# DualLink.net
KiCad netlist of a schematic drawn in Altium Designer
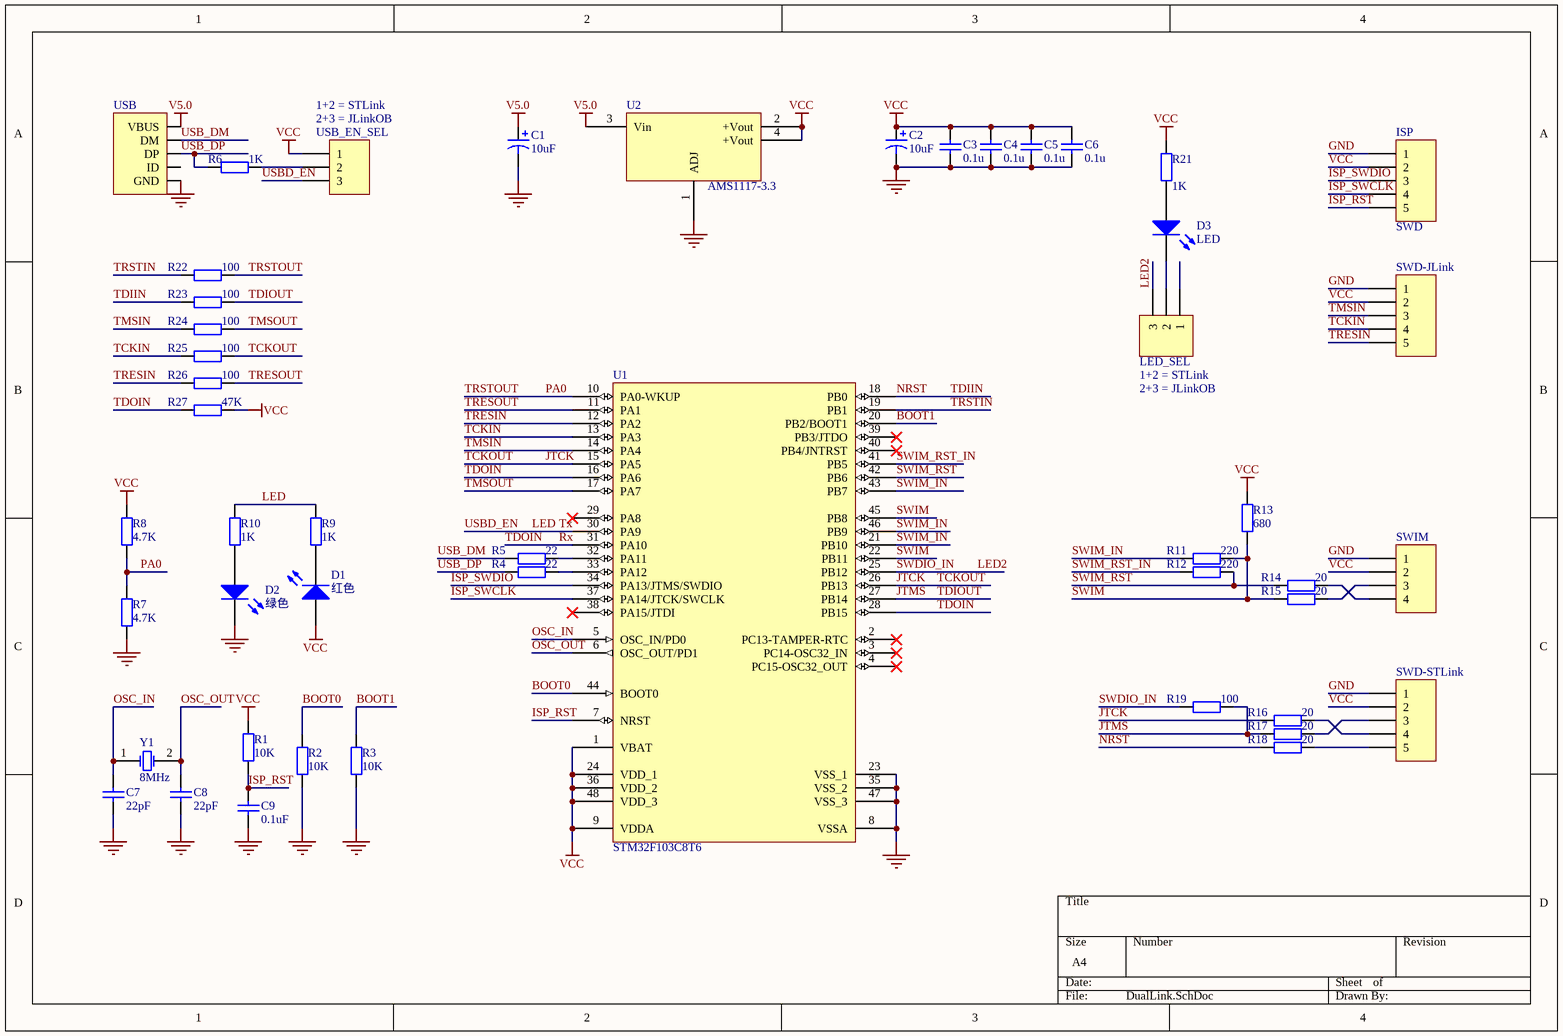
[diagram p0: DualLink.SchDoc]

(export (version "E")
  (design (tool "Eeschema 10.0.6"))
  (components
    (comp (ref "C1")
      (value "10uF")
      (footprint "C1206A")
      (description "Polarized Capacitor (Surface Mount)")
      (fields (field (name "PUBLISHER") "Altium Limited"))
      (libsource (lib "altium-import") (part "root_3_Cap Pol3_"))
    )
    (comp (ref "C2")
      (value "10uF")
      (footprint "C1206A")
      (description "Polarized Capacitor (Surface Mount)")
      (fields (field (name "PUBLISHER") "Altium Limited"))
      (libsource (lib "altium-import") (part "root_3_Cap Pol3_"))
    )
    (comp (ref "C3")
      (value "0.1u")
      (description "Capacitor")
      (fields (field (name "PUBLISHER") "Altium Limited"))
      (libsource (lib "altium-import") (part "root_3_Cap_"))
    )
    (comp (ref "C4")
      (value "0.1u")
      (description "Capacitor")
      (fields (field (name "PUBLISHER") "Altium Limited"))
      (libsource (lib "altium-import") (part "root_3_Cap_"))
    )
    (comp (ref "C5")
      (value "0.1u")
      (description "Capacitor")
      (fields (field (name "PUBLISHER") "Altium Limited"))
      (libsource (lib "altium-import") (part "root_3_Cap_"))
    )
    (comp (ref "C6")
      (value "0.1u")
      (description "Capacitor")
      (fields (field (name "PUBLISHER") "Altium Limited"))
      (libsource (lib "altium-import") (part "root_3_Cap_"))
    )
    (comp (ref "C7")
      (value "22pF")
      (footprint "C0603")
      (description "Capacitor")
      (fields (field (name "PUBLISHER") "Altium Limited"))
      (libsource (lib "altium-import") (part "root_3_Cap_"))
    )
    (comp (ref "C8")
      (value "22pF")
      (footprint "C0603")
      (description "Capacitor")
      (fields (field (name "PUBLISHER") "Altium Limited"))
      (libsource (lib "altium-import") (part "root_3_Cap_"))
    )
    (comp (ref "C9")
      (value "0.1uF")
      (footprint "C0603")
      (description "Capacitor")
      (fields (field (name "PUBLISHER") "Altium Limited"))
      (libsource (lib "altium-import") (part "root_3_Cap_"))
    )
    (comp (ref "D1")
      (value "红色")
      (footprint "LED0603")
      (description "Typical RED, GREEN, YELLOW, AMBER GaAs LED")
      (fields (field (name "PUBLISHER") "Altium Limited"))
      (libsource (lib "altium-import") (part "root_1_LED2_"))
    )
    (comp (ref "D2")
      (value "绿色")
      (footprint "LED0603")
      (description "Typical RED, GREEN, YELLOW, AMBER GaAs LED")
      (fields (field (name "PUBLISHER") "Altium Limited"))
      (libsource (lib "altium-import") (part "root_3_LED2_"))
    )
    (comp (ref "D3")
      (value "LED")
      (footprint "LED0603")
      (description "Typical RED, GREEN, YELLOW, AMBER GaAs LED")
      (fields (field (name "PUBLISHER") "Altium Limited"))
      (libsource (lib "altium-import") (part "root_3_LED2_"))
    )
    (comp (ref "ISP")
      (value "SWD")
      (footprint "HDR1X5")
      (description "Header, 5-Pin")
      (fields (field (name "PUBLISHER") "Altium Limited"))
      (libsource (lib "altium-import") (part "root_0_Header 5_"))
    )
    (comp (ref "LED_SEL")
      (value "~")
      (footprint "HDR1X3")
      (description "Header, 3-Pin")
      (fields (field (name "PUBLISHER") "Altium Limited"))
      (libsource (lib "altium-import") (part "root_3_Header 3_"))
    )
    (comp (ref "R1")
      (value "10K")
      (footprint "R0603")
      (description "Resistor")
      (fields (field (name "PUBLISHER") "Altium Limited"))
      (libsource (lib "altium-import") (part "root_1_Res2_"))
    )
    (comp (ref "R2")
      (value "10K")
      (footprint "R0603")
      (description "Resistor")
      (fields (field (name "PUBLISHER") "Altium Limited"))
      (libsource (lib "altium-import") (part "root_1_Res2_"))
    )
    (comp (ref "R3")
      (value "10K")
      (footprint "R0603")
      (description "Resistor")
      (fields (field (name "PUBLISHER") "Altium Limited"))
      (libsource (lib "altium-import") (part "root_1_Res2_"))
    )
    (comp (ref "R4")
      (value "22")
      (footprint "R0603")
      (description "Resistor")
      (fields (field (name "PUBLISHER") "Altium Limited"))
      (libsource (lib "altium-import") (part "root_2_Res2_"))
    )
    (comp (ref "R5")
      (value "22")
      (footprint "R0603")
      (description "Resistor")
      (fields (field (name "PUBLISHER") "Altium Limited"))
      (libsource (lib "altium-import") (part "root_2_Res2_"))
    )
    (comp (ref "R6")
      (value "1K")
      (footprint "R0603")
      (description "Resistor")
      (fields (field (name "PUBLISHER") "Altium Limited"))
      (libsource (lib "altium-import") (part "root_0_Res2_"))
    )
    (comp (ref "R7")
      (value "4.7K")
      (footprint "R0603")
      (description "Resistor")
      (fields (field (name "PUBLISHER") "Altium Limited"))
      (libsource (lib "altium-import") (part "root_3_Res2_"))
    )
    (comp (ref "R8")
      (value "4.7K")
      (footprint "R0603")
      (description "Resistor")
      (fields (field (name "PUBLISHER") "Altium Limited"))
      (libsource (lib "altium-import") (part "root_3_Res2_"))
    )
    (comp (ref "R9")
      (value "1K")
      (footprint "R0603")
      (description "Resistor")
      (fields (field (name "PUBLISHER") "Altium Limited"))
      (libsource (lib "altium-import") (part "root_3_Res2_"))
    )
    (comp (ref "R10")
      (value "1K")
      (footprint "R0603")
      (description "Resistor")
      (fields (field (name "PUBLISHER") "Altium Limited"))
      (libsource (lib "altium-import") (part "root_3_Res2_"))
    )
    (comp (ref "R11")
      (value "220")
      (footprint "R0603")
      (description "Resistor")
      (fields (field (name "PUBLISHER") "Altium Limited"))
      (libsource (lib "altium-import") (part "root_0_Res2_"))
    )
    (comp (ref "R12")
      (value "220")
      (footprint "R0603")
      (description "Resistor")
      (fields (field (name "PUBLISHER") "Altium Limited"))
      (libsource (lib "altium-import") (part "root_0_Res2_"))
    )
    (comp (ref "R13")
      (value "680")
      (footprint "R0603")
      (description "Resistor")
      (fields (field (name "PUBLISHER") "Altium Limited"))
      (libsource (lib "altium-import") (part "root_1_Res2_"))
    )
    (comp (ref "R14")
      (value "20")
      (footprint "R0603")
      (description "Resistor")
      (fields (field (name "PUBLISHER") "Altium Limited"))
      (libsource (lib "altium-import") (part "root_2_Res2_"))
    )
    (comp (ref "R15")
      (value "20")
      (footprint "R0603")
      (description "Resistor")
      (fields (field (name "PUBLISHER") "Altium Limited"))
      (libsource (lib "altium-import") (part "root_2_Res2_"))
    )
    (comp (ref "R16")
      (value "20")
      (footprint "R0603")
      (description "Resistor")
      (fields (field (name "PUBLISHER") "Altium Limited"))
      (libsource (lib "altium-import") (part "root_2_Res2_"))
    )
    (comp (ref "R17")
      (value "20")
      (footprint "R0603")
      (description "Resistor")
      (fields (field (name "PUBLISHER") "Altium Limited"))
      (libsource (lib "altium-import") (part "root_2_Res2_"))
    )
    (comp (ref "R18")
      (value "20")
      (footprint "R0603")
      (description "Resistor")
      (fields (field (name "PUBLISHER") "Altium Limited"))
      (libsource (lib "altium-import") (part "root_2_Res2_"))
    )
    (comp (ref "R19")
      (value "100")
      (footprint "R0603")
      (description "Resistor")
      (fields (field (name "PUBLISHER") "Altium Limited"))
      (libsource (lib "altium-import") (part "root_2_Res2_"))
    )
    (comp (ref "R21")
      (value "1K")
      (footprint "R0603")
      (description "Resistor")
      (fields (field (name "PUBLISHER") "Altium Limited"))
      (libsource (lib "altium-import") (part "root_3_Res2_"))
    )
    (comp (ref "R22")
      (value "100")
      (footprint "R0603")
      (description "Resistor")
      (fields (field (name "PUBLISHER") "Altium Limited"))
      (libsource (lib "altium-import") (part "root_0_Res2_"))
    )
    (comp (ref "R23")
      (value "100")
      (footprint "R0603")
      (description "Resistor")
      (fields (field (name "PUBLISHER") "Altium Limited"))
      (libsource (lib "altium-import") (part "root_0_Res2_"))
    )
    (comp (ref "R24")
      (value "100")
      (footprint "R0603")
      (description "Resistor")
      (fields (field (name "PUBLISHER") "Altium Limited"))
      (libsource (lib "altium-import") (part "root_0_Res2_"))
    )
    (comp (ref "R25")
      (value "100")
      (footprint "R0603")
      (description "Resistor")
      (fields (field (name "PUBLISHER") "Altium Limited"))
      (libsource (lib "altium-import") (part "root_0_Res2_"))
    )
    (comp (ref "R26")
      (value "100")
      (footprint "R0603")
      (description "Resistor")
      (fields (field (name "PUBLISHER") "Altium Limited"))
      (libsource (lib "altium-import") (part "root_0_Res2_"))
    )
    (comp (ref "R27")
      (value "47K")
      (footprint "R0603")
      (description "Resistor")
      (fields (field (name "PUBLISHER") "Altium Limited"))
      (libsource (lib "altium-import") (part "root_0_Res2_"))
    )
    (comp (ref "SWD-JLink")
      (value "SWD")
      (footprint "HDR1X5")
      (description "Header, 5-Pin")
      (fields (field (name "PUBLISHER") "Altium Limited"))
      (libsource (lib "altium-import") (part "root_0_Header 5_"))
    )
    (comp (ref "SWD-STLink")
      (value "SWD")
      (footprint "HDR1X5")
      (description "Header, 5-Pin")
      (fields (field (name "PUBLISHER") "Altium Limited"))
      (libsource (lib "altium-import") (part "root_0_Header 5_"))
    )
    (comp (ref "SWIM")
      (value "SWIM")
      (footprint "HDR1X4")
      (description "Header, 4-Pin")
      (fields (field (name "PUBLISHER") "Altium Limited"))
      (libsource (lib "altium-import") (part "root_0_Header 4_"))
    )
    (comp (ref "U1")
      (value "STM32F103C8T6")
      (footprint "LQFP48_M")
      (description "STM32 ARM-based 32-bit MCU with 64 Kbytes Flash, 48-pin LQFP, Industrial Temperature")
      (fields (field (name "PUBLISHER") "Altium Limited"))
      (libsource (lib "altium-import") (part "root_0_STM32F103C8T6_"))
    )
    (comp (ref "U2")
      (value "AMS1117-3.3")
      (footprint "SOT-223")
      (libsource (lib "altium-import") (part "root_0_LM117T_"))
    )
    (comp (ref "USB")
      (value "USB_Micro")
      (footprint "USB_MICRO_B")
      (description "USB")
      (libsource (lib "altium-import") (part "root_0_USB_Micro_"))
    )
    (comp (ref "USB_EN_SEL")
      (value "~")
      (footprint "HDR1X3")
      (description "Header, 3-Pin")
      (fields (field (name "PUBLISHER") "Altium Limited"))
      (libsource (lib "altium-import") (part "root_0_Header 3_"))
    )
    (comp (ref "Y1")
      (value "8MHz")
      (footprint "JZ")
      (description "Crystal Oscillator")
      (fields (field (name "PUBLISHER") "Altium Limited"))
      (libsource (lib "altium-import") (part "root_0_XTAL_"))
    )
  )
  (nets
    (net (code "1") (name "/BOOT0") (class "Default")
      (node (ref "R2") (pin "2") (pinfunction "2_2") (pintype "passive"))
      (node (ref "U1") (pin "44") (pinfunction "BOOT0_44") (pintype "input"))
    )
    (net (code "2") (name "/BOOT1") (class "Default")
      (node (ref "R3") (pin "2") (pinfunction "2_2") (pintype "passive"))
      (node (ref "U1") (pin "20") (pinfunction "PB2/BOOT1_20") (pintype "bidirectional"))
    )
    (net (code "3") (name "/ISP_RST") (class "Default")
      (node (ref "C9") (pin "1") (pinfunction "1_1") (pintype "passive"))
      (node (ref "ISP") (pin "5") (pinfunction "5_5") (pintype "passive"))
      (node (ref "R1") (pin "1") (pinfunction "1_1") (pintype "passive"))
      (node (ref "U1") (pin "7") (pinfunction "NRST_7") (pintype "bidirectional"))
    )
    (net (code "4") (name "/ISP_SWCLK") (class "Default")
      (node (ref "ISP") (pin "4") (pinfunction "4_4") (pintype "passive"))
      (node (ref "U1") (pin "37") (pinfunction "PA14/JTCK/SWCLK_37") (pintype "bidirectional"))
    )
    (net (code "5") (name "/ISP_SWDIO") (class "Default")
      (node (ref "ISP") (pin "3") (pinfunction "3_3") (pintype "passive"))
      (node (ref "U1") (pin "34") (pinfunction "PA13/JTMS/SWDIO_34") (pintype "bidirectional"))
    )
    (net (code "6") (name "/JTCK") (class "Default")
      (node (ref "R16") (pin "2") (pinfunction "2_2") (pintype "passive"))
      (node (ref "R25") (pin "2") (pinfunction "2_2") (pintype "passive"))
      (node (ref "U1") (pin "15") (pinfunction "PA5_15") (pintype "bidirectional"))
      (node (ref "U1") (pin "26") (pinfunction "PB13_26") (pintype "bidirectional"))
    )
    (net (code "7") (name "/JTMS") (class "Default")
      (node (ref "R17") (pin "2") (pinfunction "2_2") (pintype "passive"))
      (node (ref "R19") (pin "1") (pinfunction "1_1") (pintype "passive"))
      (node (ref "R23") (pin "2") (pinfunction "2_2") (pintype "passive"))
      (node (ref "U1") (pin "27") (pinfunction "PB14_27") (pintype "bidirectional"))
    )
    (net (code "8") (name "/LED") (class "Default")
      (node (ref "R10") (pin "1") (pinfunction "1_1") (pintype "passive"))
      (node (ref "R9") (pin "1") (pinfunction "1_1") (pintype "passive"))
      (node (ref "U1") (pin "30") (pinfunction "PA9_30") (pintype "bidirectional"))
      (node (ref "USB_EN_SEL") (pin "3") (pinfunction "3_3") (pintype "passive"))
    )
    (net (code "9") (name "/LED2") (class "Default")
      (node (ref "LED_SEL") (pin "3") (pinfunction "3_3") (pintype "passive"))
      (node (ref "R19") (pin "2") (pinfunction "2_2") (pintype "passive"))
      (node (ref "U1") (pin "25") (pinfunction "PB12_25") (pintype "bidirectional"))
    )
    (net (code "10") (name "/NRST") (class "Default")
      (node (ref "R18") (pin "2") (pinfunction "2_2") (pintype "passive"))
      (node (ref "R23") (pin "1") (pinfunction "1_1") (pintype "passive"))
      (node (ref "U1") (pin "18") (pinfunction "PB0_18") (pintype "bidirectional"))
    )
    (net (code "11") (name "/OSC_IN") (class "Default")
      (node (ref "C7") (pin "1") (pinfunction "1_1") (pintype "passive"))
      (node (ref "U1") (pin "5") (pinfunction "OSC_IN/PD0_5") (pintype "input"))
      (node (ref "Y1") (pin "1") (pinfunction "OSC1_1") (pintype "passive"))
    )
    (net (code "12") (name "/OSC_OUT") (class "Default")
      (node (ref "C8") (pin "1") (pinfunction "1_1") (pintype "passive"))
      (node (ref "U1") (pin "6") (pinfunction "OSC_OUT/PD1_6") (pintype "output"))
      (node (ref "Y1") (pin "2") (pinfunction "OSC2_2") (pintype "passive"))
    )
    (net (code "13") (name "/PA0") (class "Default")
      (node (ref "R22") (pin "2") (pinfunction "2_2") (pintype "passive"))
      (node (ref "R7") (pin "1") (pinfunction "1_1") (pintype "passive"))
      (node (ref "R8") (pin "2") (pinfunction "2_2") (pintype "passive"))
      (node (ref "U1") (pin "10") (pinfunction "PA0-WKUP_10") (pintype "bidirectional"))
    )
    (net (code "14") (name "/Rx") (class "Default")
      (node (ref "R27") (pin "1") (pinfunction "1_1") (pintype "passive"))
      (node (ref "U1") (pin "16") (pinfunction "PA6_16") (pintype "bidirectional"))
      (node (ref "U1") (pin "28") (pinfunction "PB15_28") (pintype "bidirectional"))
      (node (ref "U1") (pin "31") (pinfunction "PA10_31") (pintype "bidirectional"))
    )
    (net (code "15") (name "/SWIM") (class "Default")
      (node (ref "R11") (pin "2") (pinfunction "2_2") (pintype "passive"))
      (node (ref "R13") (pin "1") (pinfunction "1_1") (pintype "passive"))
      (node (ref "R15") (pin "2") (pinfunction "2_2") (pintype "passive"))
      (node (ref "U1") (pin "22") (pinfunction "PB11_22") (pintype "bidirectional"))
      (node (ref "U1") (pin "45") (pinfunction "PB8_45") (pintype "bidirectional"))
    )
    (net (code "16") (name "/SWIM_IN") (class "Default")
      (node (ref "R11") (pin "1") (pinfunction "1_1") (pintype "passive"))
      (node (ref "U1") (pin "21") (pinfunction "PB10_21") (pintype "bidirectional"))
      (node (ref "U1") (pin "43") (pinfunction "PB7_43") (pintype "bidirectional"))
      (node (ref "U1") (pin "46") (pinfunction "PB9_46") (pintype "bidirectional"))
    )
    (net (code "17") (name "/SWIM_RST") (class "Default")
      (node (ref "R12") (pin "2") (pinfunction "2_2") (pintype "passive"))
      (node (ref "R14") (pin "2") (pinfunction "2_2") (pintype "passive"))
      (node (ref "U1") (pin "42") (pinfunction "PB6_42") (pintype "bidirectional"))
    )
    (net (code "18") (name "/SWIM_RST_IN") (class "Default")
      (node (ref "R12") (pin "1") (pinfunction "1_1") (pintype "passive"))
      (node (ref "U1") (pin "41") (pinfunction "PB5_41") (pintype "bidirectional"))
    )
    (net (code "19") (name "/TCKIN") (class "Default")
      (node (ref "R25") (pin "1") (pinfunction "1_1") (pintype "passive"))
      (node (ref "SWD-JLink") (pin "4") (pinfunction "4_4") (pintype "passive"))
      (node (ref "U1") (pin "13") (pinfunction "PA3_13") (pintype "bidirectional"))
    )
    (net (code "20") (name "/TMSIN") (class "Default")
      (node (ref "R24") (pin "1") (pinfunction "1_1") (pintype "passive"))
      (node (ref "SWD-JLink") (pin "3") (pinfunction "3_3") (pintype "passive"))
      (node (ref "U1") (pin "14") (pinfunction "PA4_14") (pintype "bidirectional"))
    )
    (net (code "21") (name "/TMSOUT") (class "Default")
      (node (ref "R24") (pin "2") (pinfunction "2_2") (pintype "passive"))
      (node (ref "U1") (pin "17") (pinfunction "PA7_17") (pintype "bidirectional"))
    )
    (net (code "22") (name "/TRESIN") (class "Default")
      (node (ref "R26") (pin "1") (pinfunction "1_1") (pintype "passive"))
      (node (ref "SWD-JLink") (pin "5") (pinfunction "5_5") (pintype "passive"))
      (node (ref "U1") (pin "12") (pinfunction "PA2_12") (pintype "bidirectional"))
    )
    (net (code "23") (name "/TRESOUT") (class "Default")
      (node (ref "R26") (pin "2") (pinfunction "2_2") (pintype "passive"))
      (node (ref "U1") (pin "11") (pinfunction "PA1_11") (pintype "bidirectional"))
    )
    (net (code "24") (name "/TRSTIN") (class "Default")
      (node (ref "R22") (pin "1") (pinfunction "1_1") (pintype "passive"))
      (node (ref "U1") (pin "19") (pinfunction "PB1_19") (pintype "bidirectional"))
    )
    (net (code "25") (name "/USB_DM") (class "Default")
      (node (ref "R5") (pin "2") (pinfunction "2_2") (pintype "passive"))
      (node (ref "USB") (pin "2") (pinfunction "DM_2") (pintype "passive"))
    )
    (net (code "26") (name "/USB_DP") (class "Default")
      (node (ref "R4") (pin "2") (pinfunction "2_2") (pintype "passive"))
      (node (ref "R6") (pin "1") (pinfunction "1_1") (pintype "passive"))
      (node (ref "USB") (pin "3") (pinfunction "DP_3") (pintype "passive"))
    )
    (net (code "27") (name "GND") (class "Default")
      (node (ref "C1") (pin "2") (pinfunction "2_2") (pintype "passive"))
      (node (ref "C2") (pin "2") (pinfunction "2_2") (pintype "passive"))
      (node (ref "C3") (pin "2") (pinfunction "2_2") (pintype "passive"))
      (node (ref "C4") (pin "2") (pinfunction "2_2") (pintype "passive"))
      (node (ref "C5") (pin "2") (pinfunction "2_2") (pintype "passive"))
      (node (ref "C6") (pin "2") (pinfunction "2_2") (pintype "passive"))
      (node (ref "C7") (pin "2") (pinfunction "2_2") (pintype "passive"))
      (node (ref "C8") (pin "2") (pinfunction "2_2") (pintype "passive"))
      (node (ref "C9") (pin "2") (pinfunction "2_2") (pintype "passive"))
      (node (ref "D2") (pin "2") (pinfunction "K_2") (pintype "passive"))
      (node (ref "ISP") (pin "1") (pinfunction "1_1") (pintype "passive"))
      (node (ref "R2") (pin "1") (pinfunction "1_1") (pintype "passive"))
      (node (ref "R3") (pin "1") (pinfunction "1_1") (pintype "passive"))
      (node (ref "R7") (pin "2") (pinfunction "2_2") (pintype "passive"))
      (node (ref "SWD-JLink") (pin "1") (pinfunction "1_1") (pintype "passive"))
      (node (ref "SWD-STLink") (pin "1") (pinfunction "1_1") (pintype "passive"))
      (node (ref "SWIM") (pin "1") (pinfunction "1_1") (pintype "passive"))
      (node (ref "U1") (pin "23") (pinfunction "VSS_1_23") (pintype "power_in"))
      (node (ref "U1") (pin "35") (pinfunction "VSS_2_35") (pintype "power_in"))
      (node (ref "U1") (pin "47") (pinfunction "VSS_3_47") (pintype "power_in"))
      (node (ref "U1") (pin "8") (pinfunction "VSSA_8") (pintype "power_in"))
      (node (ref "U2") (pin "1") (pinfunction "ADJ_1") (pintype "passive"))
      (node (ref "USB") (pin "5") (pinfunction "GND_5") (pintype "passive"))
    )
    (net (code "28") (name "Net-(D1-K)") (class "Default")
      (node (ref "D1") (pin "2") (pinfunction "K_2") (pintype "passive"))
      (node (ref "R9") (pin "2") (pinfunction "2_2") (pintype "passive"))
    )
    (net (code "29") (name "Net-(D2-A)") (class "Default")
      (node (ref "D2") (pin "1") (pinfunction "A_1") (pintype "passive"))
      (node (ref "R10") (pin "2") (pinfunction "2_2") (pintype "passive"))
    )
    (net (code "30") (name "Net-(D3-A)") (class "Default")
      (node (ref "D3") (pin "1") (pinfunction "A_1") (pintype "passive"))
      (node (ref "R21") (pin "2") (pinfunction "2_2") (pintype "passive"))
    )
    (net (code "31") (name "Net-(D3-K)") (class "Default")
      (node (ref "D3") (pin "2") (pinfunction "K_2") (pintype "passive"))
      (node (ref "LED_SEL") (pin "2") (pinfunction "2_2") (pintype "passive"))
    )
    (net (code "32") (name "Net-(R6-Pad2)") (class "Default")
      (node (ref "R6") (pin "2") (pinfunction "2_2") (pintype "passive"))
      (node (ref "USB_EN_SEL") (pin "2") (pinfunction "2_2") (pintype "passive"))
    )
    (net (code "33") (name "Net-(R14-Pad1)") (class "Default")
      (node (ref "R14") (pin "1") (pinfunction "1_1") (pintype "passive"))
      (node (ref "SWIM") (pin "4") (pinfunction "4_4") (pintype "passive"))
    )
    (net (code "34") (name "Net-(R15-Pad1)") (class "Default")
      (node (ref "R15") (pin "1") (pinfunction "1_1") (pintype "passive"))
      (node (ref "SWIM") (pin "3") (pinfunction "3_3") (pintype "passive"))
    )
    (net (code "35") (name "Net-(R16-Pad1)") (class "Default")
      (node (ref "R16") (pin "1") (pinfunction "1_1") (pintype "passive"))
      (node (ref "SWD-STLink") (pin "4") (pinfunction "4_4") (pintype "passive"))
    )
    (net (code "36") (name "Net-(R17-Pad1)") (class "Default")
      (node (ref "R17") (pin "1") (pinfunction "1_1") (pintype "passive"))
      (node (ref "SWD-STLink") (pin "3") (pinfunction "3_3") (pintype "passive"))
    )
    (net (code "37") (name "Net-(R18-Pad1)") (class "Default")
      (node (ref "R18") (pin "1") (pinfunction "1_1") (pintype "passive"))
      (node (ref "SWD-STLink") (pin "5") (pinfunction "5_5") (pintype "passive"))
    )
    (net (code "38") (name "Net-(U1-PA11)") (class "Default")
      (node (ref "R5") (pin "1") (pinfunction "1_1") (pintype "passive"))
      (node (ref "U1") (pin "32") (pinfunction "PA11_32") (pintype "bidirectional"))
    )
    (net (code "39") (name "Net-(U1-PA12)") (class "Default")
      (node (ref "R4") (pin "1") (pinfunction "1_1") (pintype "passive"))
      (node (ref "U1") (pin "33") (pinfunction "PA12_33") (pintype "bidirectional"))
    )
    (net (code "40") (name "V5.0") (class "Default")
      (node (ref "C1") (pin "1") (pinfunction "1_1") (pintype "passive"))
      (node (ref "U2") (pin "3") (pinfunction "Vin_3") (pintype "passive"))
      (node (ref "USB") (pin "1") (pinfunction "VBUS_1") (pintype "passive"))
    )
    (net (code "41") (name "VCC") (class "Default")
      (node (ref "C2") (pin "1") (pinfunction "1_1") (pintype "passive"))
      (node (ref "C3") (pin "1") (pinfunction "1_1") (pintype "passive"))
      (node (ref "C4") (pin "1") (pinfunction "1_1") (pintype "passive"))
      (node (ref "C5") (pin "1") (pinfunction "1_1") (pintype "passive"))
      (node (ref "C6") (pin "1") (pinfunction "1_1") (pintype "passive"))
      (node (ref "D1") (pin "1") (pinfunction "A_1") (pintype "passive"))
      (node (ref "ISP") (pin "2") (pinfunction "2_2") (pintype "passive"))
      (node (ref "R1") (pin "2") (pinfunction "2_2") (pintype "passive"))
      (node (ref "R13") (pin "2") (pinfunction "2_2") (pintype "passive"))
      (node (ref "R21") (pin "1") (pinfunction "1_1") (pintype "passive"))
      (node (ref "R27") (pin "2") (pinfunction "2_2") (pintype "passive"))
      (node (ref "R8") (pin "1") (pinfunction "1_1") (pintype "passive"))
      (node (ref "SWD-JLink") (pin "2") (pinfunction "2_2") (pintype "passive"))
      (node (ref "SWD-STLink") (pin "2") (pinfunction "2_2") (pintype "passive"))
      (node (ref "SWIM") (pin "2") (pinfunction "2_2") (pintype "passive"))
      (node (ref "U1") (pin "1") (pinfunction "VBAT_1") (pintype "power_in"))
      (node (ref "U1") (pin "24") (pinfunction "VDD_1_24") (pintype "power_in"))
      (node (ref "U1") (pin "36") (pinfunction "VDD_2_36") (pintype "power_in"))
      (node (ref "U1") (pin "48") (pinfunction "VDD_3_48") (pintype "power_in"))
      (node (ref "U1") (pin "9") (pinfunction "VDDA_9") (pintype "power_in"))
      (node (ref "U2") (pin "2") (pinfunction "+Vout_2") (pintype "passive"))
      (node (ref "U2") (pin "4") (pinfunction "+Vout_4") (pintype "passive"))
      (node (ref "USB_EN_SEL") (pin "1") (pinfunction "1_1") (pintype "passive"))
    )
    (net (code "42") (name "unconnected-(LED_SEL-Pad1)") (class "Default")
      (node (ref "LED_SEL") (pin "1") (pinfunction "1_1") (pintype "passive"))
    )
    (net (code "43") (name "unconnected-(U1-PA8-Pad29)") (class "Default")
      (node (ref "U1") (pin "29") (pinfunction "PA8_29") (pintype "bidirectional+no_connect"))
    )
    (net (code "44") (name "unconnected-(U1-PA15{slash}JTDI-Pad38)") (class "Default")
      (node (ref "U1") (pin "38") (pinfunction "PA15/JTDI_38") (pintype "bidirectional+no_connect"))
    )
    (net (code "45") (name "unconnected-(U1-PB3{slash}JTDO-Pad39)") (class "Default")
      (node (ref "U1") (pin "39") (pinfunction "PB3/JTDO_39") (pintype "bidirectional+no_connect"))
    )
    (net (code "46") (name "unconnected-(U1-PB4{slash}JNTRST-Pad40)") (class "Default")
      (node (ref "U1") (pin "40") (pinfunction "PB4/JNTRST_40") (pintype "bidirectional+no_connect"))
    )
    (net (code "47") (name "unconnected-(U1-PC13-TAMPER-RTC-Pad2)") (class "Default")
      (node (ref "U1") (pin "2") (pinfunction "PC13-TAMPER-RTC_2") (pintype "bidirectional+no_connect"))
    )
    (net (code "48") (name "unconnected-(U1-PC14-OSC32_IN-Pad3)") (class "Default")
      (node (ref "U1") (pin "3") (pinfunction "PC14-OSC32_IN_3") (pintype "bidirectional+no_connect"))
    )
    (net (code "49") (name "unconnected-(U1-PC15-OSC32_OUT-Pad4)") (class "Default")
      (node (ref "U1") (pin "4") (pinfunction "PC15-OSC32_OUT_4") (pintype "bidirectional+no_connect"))
    )
    (net (code "50") (name "unconnected-(USB-ID-Pad4)") (class "Default")
      (node (ref "USB") (pin "4") (pinfunction "ID_4") (pintype "passive"))
    )
  )
)
